# rapidshark-half-assed-half-h-bridge-mk-2.net
KiCad netlist of a schematic drawn in EAGLE
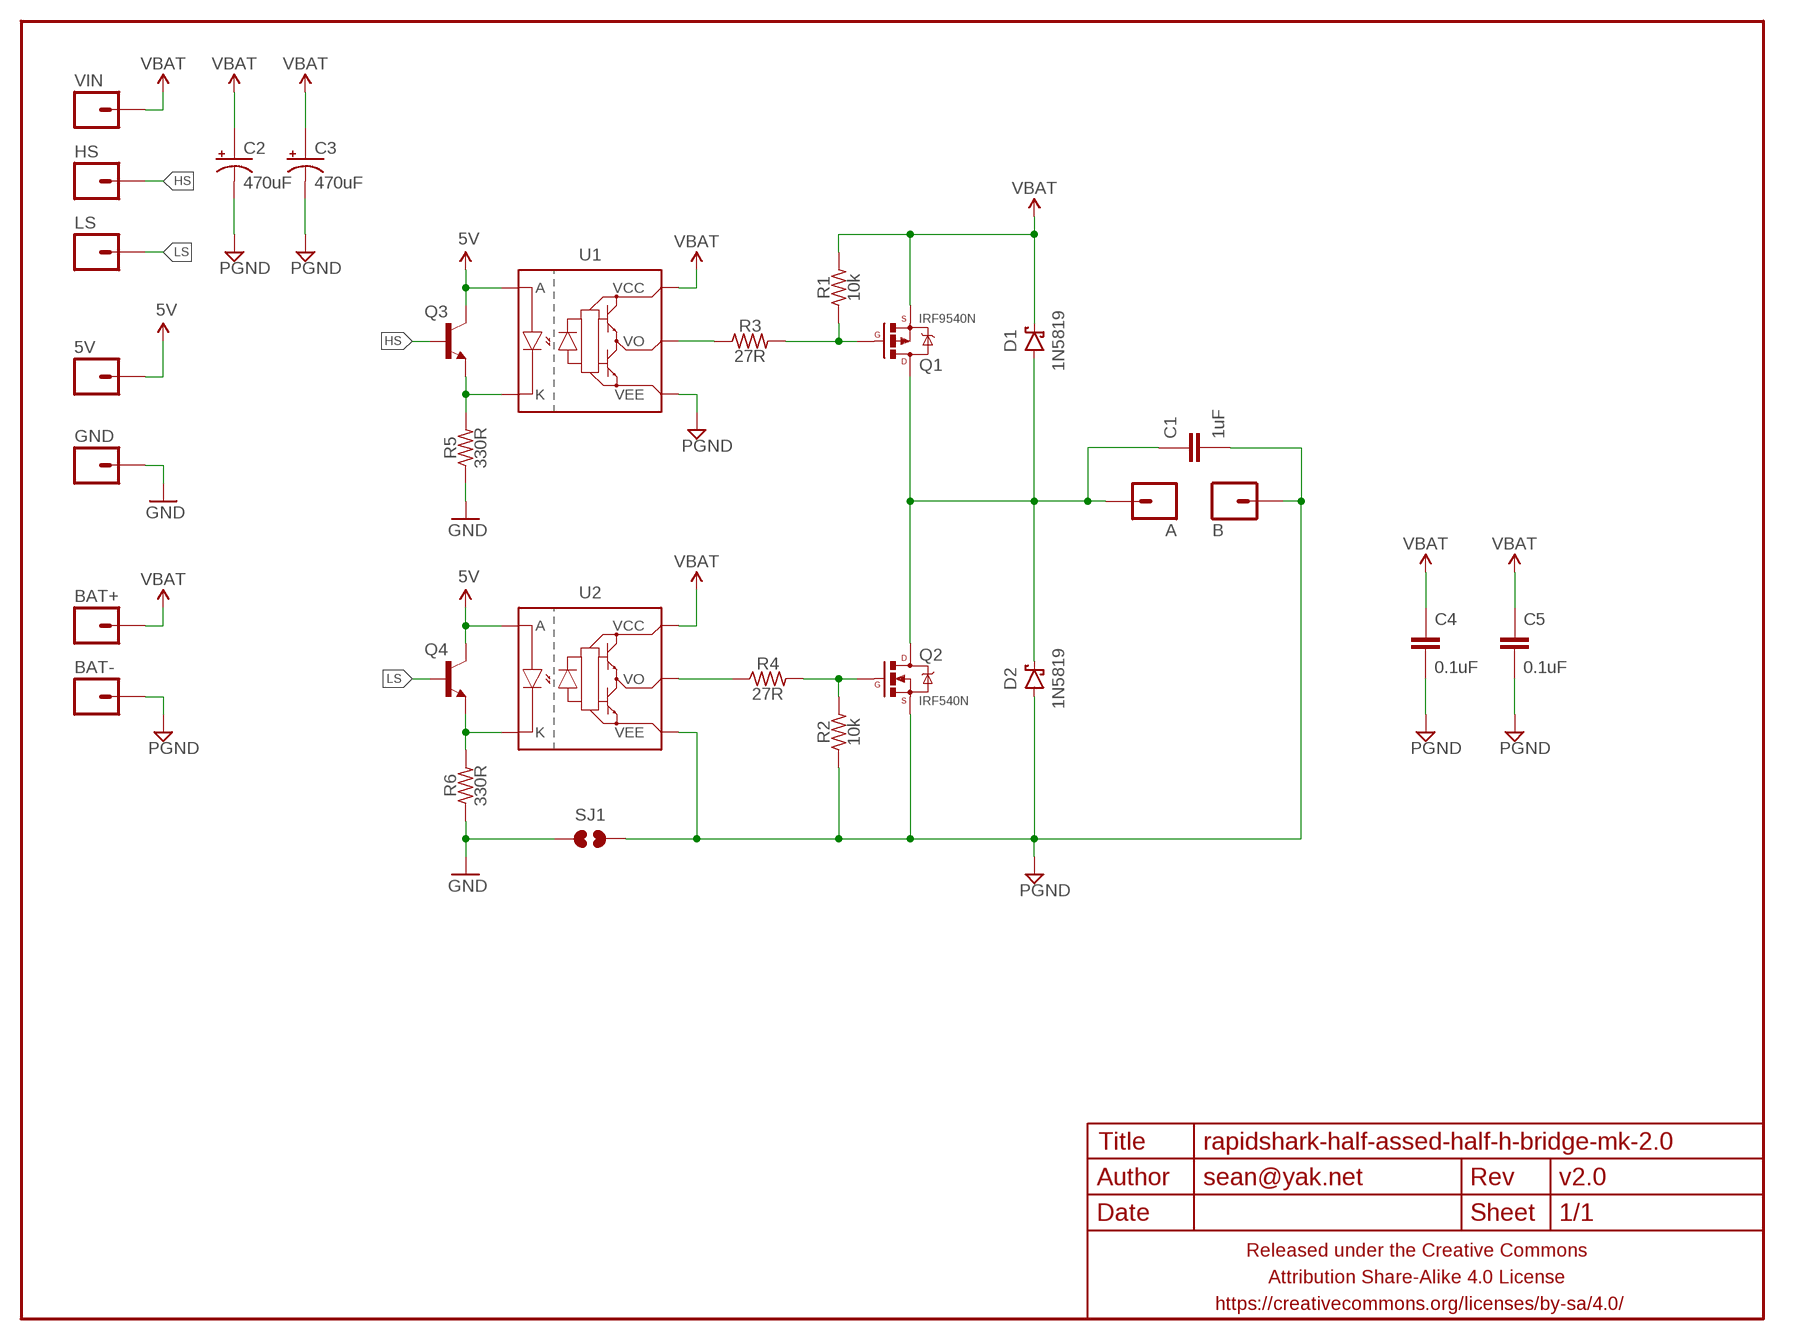
[diagram p0: schematic, sheet 1]

(export (version "E")
  (design (tool "Eeschema 10.0.6"))
  (components
    (comp (ref "5V")
      (value "M01PTH")
      (footprint "eagle-import:1X01")
      (libsource (lib "eagle-import") (part "M01PTH"))
    )
    (comp (ref "A")
      (value "M01PTH-1.9MM")
      (footprint "eagle-import:1X01-1.9MM-CIR")
      (libsource (lib "eagle-import") (part "M01PTH-1.9MM"))
    )
    (comp (ref "B")
      (value "M01PTH-1.9MM")
      (footprint "eagle-import:1X01-1.9MM-CIR")
      (libsource (lib "eagle-import") (part "M01PTH-1.9MM"))
    )
    (comp (ref "BAT+")
      (value "M01PTH-1.9MM")
      (footprint "eagle-import:1X01-1.9MM-CIR")
      (libsource (lib "eagle-import") (part "M01PTH-1.9MM"))
    )
    (comp (ref "BAT-")
      (value "M01PTH-1.9MM")
      (footprint "eagle-import:1X01-1.9MM-CIR")
      (libsource (lib "eagle-import") (part "M01PTH-1.9MM"))
    )
    (comp (ref "C1")
      (value "1uF")
      (footprint "eagle-import:C0603-TIGHTER")
      (libsource (lib "eagle-import") (part "CAPACITOR-CERAMICC0603-TIGHTER"))
    )
    (comp (ref "C2")
      (value "470uF")
      (footprint "eagle-import:E5-10,5")
      (libsource (lib "eagle-import") (part "CAPACITOR-POLARIZEDE5-10.5"))
    )
    (comp (ref "C3")
      (value "470uF")
      (footprint "eagle-import:E5-10,5")
      (libsource (lib "eagle-import") (part "CAPACITOR-POLARIZEDE5-10.5"))
    )
    (comp (ref "C4")
      (value "0.1uF")
      (footprint "eagle-import:C0603-TIGHTER")
      (libsource (lib "eagle-import") (part "CAPACITOR-CERAMICC0603-TIGHTER"))
    )
    (comp (ref "C5")
      (value "0.1uF")
      (footprint "eagle-import:C0603-TIGHTER")
      (libsource (lib "eagle-import") (part "CAPACITOR-CERAMICC0603-TIGHTER"))
    )
    (comp (ref "D1")
      (value "1N5819")
      (footprint "eagle-import:SMA-DIODE-SCHOTTKY")
      (libsource (lib "eagle-import") (part "DIODE-SCHOTTKYSMA"))
    )
    (comp (ref "D2")
      (value "1N5819")
      (footprint "eagle-import:SMA-DIODE-SCHOTTKY")
      (libsource (lib "eagle-import") (part "DIODE-SCHOTTKYSMA"))
    )
    (comp (ref "FRAME1")
      (value "FRAME-LETTERNO_PACKAGE")
      (footprint "eagle-import:DUMMY")
      (fields (field (name "DESIGNER") "sean@yak.net") (field (name "VERSION") "v2.0"))
      (libsource (lib "eagle-import") (part "FRAME-LETTERNO_PACKAGE"))
    )
    (comp (ref "GND")
      (value "M01PTH")
      (footprint "eagle-import:1X01")
      (libsource (lib "eagle-import") (part "M01PTH"))
    )
    (comp (ref "HS")
      (value "M01PTH")
      (footprint "eagle-import:1X01")
      (libsource (lib "eagle-import") (part "M01PTH"))
    )
    (comp (ref "LS")
      (value "M01PTH")
      (footprint "eagle-import:1X01")
      (libsource (lib "eagle-import") (part "M01PTH"))
    )
    (comp (ref "Q1")
      (value "IRF9540N")
      (footprint "eagle-import:D2PAK")
      (libsource (lib "eagle-import") (part "MOSFET-PCHANNELD2PAK"))
    )
    (comp (ref "Q2")
      (value "IRF540N")
      (footprint "eagle-import:D2PAK")
      (libsource (lib "eagle-import") (part "MOSFET-NCHANNELD2PAK"))
    )
    (comp (ref "Q3")
      (value "TRANSISTOR_NPNMMBT2222A")
      (footprint "eagle-import:SOT23")
      (libsource (lib "eagle-import") (part "TRANSISTOR_NPNMMBT2222A"))
    )
    (comp (ref "Q4")
      (value "TRANSISTOR_NPNMMBT2222A")
      (footprint "eagle-import:SOT23")
      (libsource (lib "eagle-import") (part "TRANSISTOR_NPNMMBT2222A"))
    )
    (comp (ref "R1")
      (value "10k")
      (footprint "eagle-import:R0603-TIGHTER")
      (libsource (lib "eagle-import") (part "RESISTORR0603-TIGHTER"))
    )
    (comp (ref "R2")
      (value "10k")
      (footprint "eagle-import:R0603-TIGHTER")
      (libsource (lib "eagle-import") (part "RESISTORR0603-TIGHTER"))
    )
    (comp (ref "R3")
      (value "27R")
      (footprint "eagle-import:R0603-TIGHTER")
      (libsource (lib "eagle-import") (part "RESISTORR0603-TIGHTER"))
    )
    (comp (ref "R4")
      (value "27R")
      (footprint "eagle-import:R0603-TIGHTER")
      (libsource (lib "eagle-import") (part "RESISTORR0603-TIGHTER"))
    )
    (comp (ref "R5")
      (value "330R")
      (footprint "eagle-import:R0603-TIGHTER")
      (libsource (lib "eagle-import") (part "RESISTORR0603-TIGHTER"))
    )
    (comp (ref "R6")
      (value "330R")
      (footprint "eagle-import:R0603-TIGHTER")
      (libsource (lib "eagle-import") (part "RESISTORR0603-TIGHTER"))
    )
    (comp (ref "SJ1")
      (value "JUMPER-PAD-2-NO")
      (footprint "eagle-import:PAD-JUMPER-2-NO_NO_SILK")
      (libsource (lib "eagle-import") (part "JUMPER-PAD-2-NO"))
    )
    (comp (ref "U1")
      (value "OPTOISOLATOR-GATEDRIVERSOIC05")
      (footprint "eagle-import:SO05")
      (libsource (lib "eagle-import") (part "OPTOISOLATOR-GATEDRIVERSOIC05"))
    )
    (comp (ref "U2")
      (value "OPTOISOLATOR-GATEDRIVERSOIC05")
      (footprint "eagle-import:SO05")
      (libsource (lib "eagle-import") (part "OPTOISOLATOR-GATEDRIVERSOIC05"))
    )
    (comp (ref "VIN")
      (value "M01PTH")
      (footprint "eagle-import:1X01")
      (libsource (lib "eagle-import") (part "M01PTH"))
    )
  )
  (nets
    (net (code "1") (name "5V") (class "Default")
      (node (ref "5V") (pin "1") (pinfunction "1_1") (pintype "passive"))
      (node (ref "Q3") (pin "3") (pinfunction "C_3") (pintype "passive"))
      (node (ref "Q4") (pin "3") (pinfunction "C_3") (pintype "passive"))
      (node (ref "U1") (pin "1") (pinfunction "A_1") (pintype "bidirectional"))
      (node (ref "U2") (pin "1") (pinfunction "A_1") (pintype "bidirectional"))
    )
    (net (code "2") (name "GND") (class "Default")
      (node (ref "GND") (pin "1") (pinfunction "1_1") (pintype "passive"))
      (node (ref "R5") (pin "1") (pinfunction "1_1") (pintype "passive"))
      (node (ref "R6") (pin "1") (pinfunction "1_1") (pintype "passive"))
      (node (ref "SJ1") (pin "1") (pinfunction "1_1") (pintype "passive"))
    )
    (net (code "3") (name "HS") (class "Default")
      (node (ref "HS") (pin "1") (pinfunction "1_1") (pintype "passive"))
      (node (ref "Q3") (pin "1") (pinfunction "B_1") (pintype "passive"))
    )
    (net (code "4") (name "LS") (class "Default")
      (node (ref "LS") (pin "1") (pinfunction "1_1") (pintype "passive"))
      (node (ref "Q4") (pin "1") (pinfunction "B_1") (pintype "passive"))
    )
    (net (code "5") (name "Net-(A-1)") (class "Default")
      (node (ref "A") (pin "P$1") (pinfunction "1_P$1") (pintype "passive"))
      (node (ref "C1") (pin "1") (pinfunction "1_1") (pintype "passive"))
      (node (ref "D1") (pin "A") (pinfunction "A_A") (pintype "passive"))
      (node (ref "D2") (pin "C") (pinfunction "C_C") (pintype "passive"))
      (node (ref "Q1") (pin "D") (pinfunction "D_D") (pintype "passive"))
      (node (ref "Q2") (pin "D") (pinfunction "D_D") (pintype "passive"))
    )
    (net (code "6") (name "Net-(Q1-PadG)") (class "Default")
      (node (ref "Q1") (pin "G") (pinfunction "G_G") (pintype "passive"))
      (node (ref "R1") (pin "1") (pinfunction "1_1") (pintype "passive"))
      (node (ref "R3") (pin "2") (pinfunction "2_2") (pintype "passive"))
    )
    (net (code "7") (name "Net-(Q2-PadG)") (class "Default")
      (node (ref "Q2") (pin "G") (pinfunction "G_G") (pintype "passive"))
      (node (ref "R2") (pin "2") (pinfunction "2_2") (pintype "passive"))
      (node (ref "R4") (pin "2") (pinfunction "2_2") (pintype "passive"))
    )
    (net (code "8") (name "Net-(Q3-E)") (class "Default")
      (node (ref "Q3") (pin "2") (pinfunction "E_2") (pintype "passive"))
      (node (ref "R5") (pin "2") (pinfunction "2_2") (pintype "passive"))
      (node (ref "U1") (pin "3") (pinfunction "K_3") (pintype "bidirectional"))
    )
    (net (code "9") (name "Net-(Q4-E)") (class "Default")
      (node (ref "Q4") (pin "2") (pinfunction "E_2") (pintype "passive"))
      (node (ref "R6") (pin "2") (pinfunction "2_2") (pintype "passive"))
      (node (ref "U2") (pin "3") (pinfunction "K_3") (pintype "bidirectional"))
    )
    (net (code "10") (name "Net-(U1-VO)") (class "Default")
      (node (ref "R3") (pin "1") (pinfunction "1_1") (pintype "passive"))
      (node (ref "U1") (pin "5") (pinfunction "VO_5") (pintype "bidirectional"))
    )
    (net (code "11") (name "Net-(U2-VO)") (class "Default")
      (node (ref "R4") (pin "1") (pinfunction "1_1") (pintype "passive"))
      (node (ref "U2") (pin "5") (pinfunction "VO_5") (pintype "bidirectional"))
    )
    (net (code "12") (name "PGND") (class "Default")
      (node (ref "B") (pin "P$1") (pinfunction "1_P$1") (pintype "passive"))
      (node (ref "BAT-") (pin "P$1") (pinfunction "1_P$1") (pintype "passive"))
      (node (ref "C1") (pin "2") (pinfunction "2_2") (pintype "passive"))
      (node (ref "C2") (pin "-") (pinfunction "-_-") (pintype "passive"))
      (node (ref "C3") (pin "-") (pinfunction "-_-") (pintype "passive"))
      (node (ref "C4") (pin "2") (pinfunction "2_2") (pintype "passive"))
      (node (ref "C5") (pin "2") (pinfunction "2_2") (pintype "passive"))
      (node (ref "D2") (pin "A") (pinfunction "A_A") (pintype "passive"))
      (node (ref "Q2") (pin "S") (pinfunction "S_S") (pintype "passive"))
      (node (ref "R2") (pin "1") (pinfunction "1_1") (pintype "passive"))
      (node (ref "SJ1") (pin "2") (pinfunction "2_2") (pintype "passive"))
      (node (ref "U1") (pin "4") (pinfunction "VEE_4") (pintype "bidirectional"))
      (node (ref "U2") (pin "4") (pinfunction "VEE_4") (pintype "bidirectional"))
    )
    (net (code "13") (name "VBAT") (class "Default")
      (node (ref "BAT+") (pin "P$1") (pinfunction "1_P$1") (pintype "passive"))
      (node (ref "C2") (pin "+") (pinfunction "+_+") (pintype "passive"))
      (node (ref "C3") (pin "+") (pinfunction "+_+") (pintype "passive"))
      (node (ref "C4") (pin "1") (pinfunction "1_1") (pintype "passive"))
      (node (ref "C5") (pin "1") (pinfunction "1_1") (pintype "passive"))
      (node (ref "D1") (pin "C") (pinfunction "C_C") (pintype "passive"))
      (node (ref "Q1") (pin "S") (pinfunction "S_S") (pintype "passive"))
      (node (ref "R1") (pin "2") (pinfunction "2_2") (pintype "passive"))
      (node (ref "U1") (pin "6") (pinfunction "VCC_6") (pintype "bidirectional"))
      (node (ref "U2") (pin "6") (pinfunction "VCC_6") (pintype "bidirectional"))
      (node (ref "VIN") (pin "1") (pinfunction "1_1") (pintype "passive"))
    )
  )
)
